# ATTAMI-V0_00.net
KiCad netlist of a schematic drawn in EAGLE
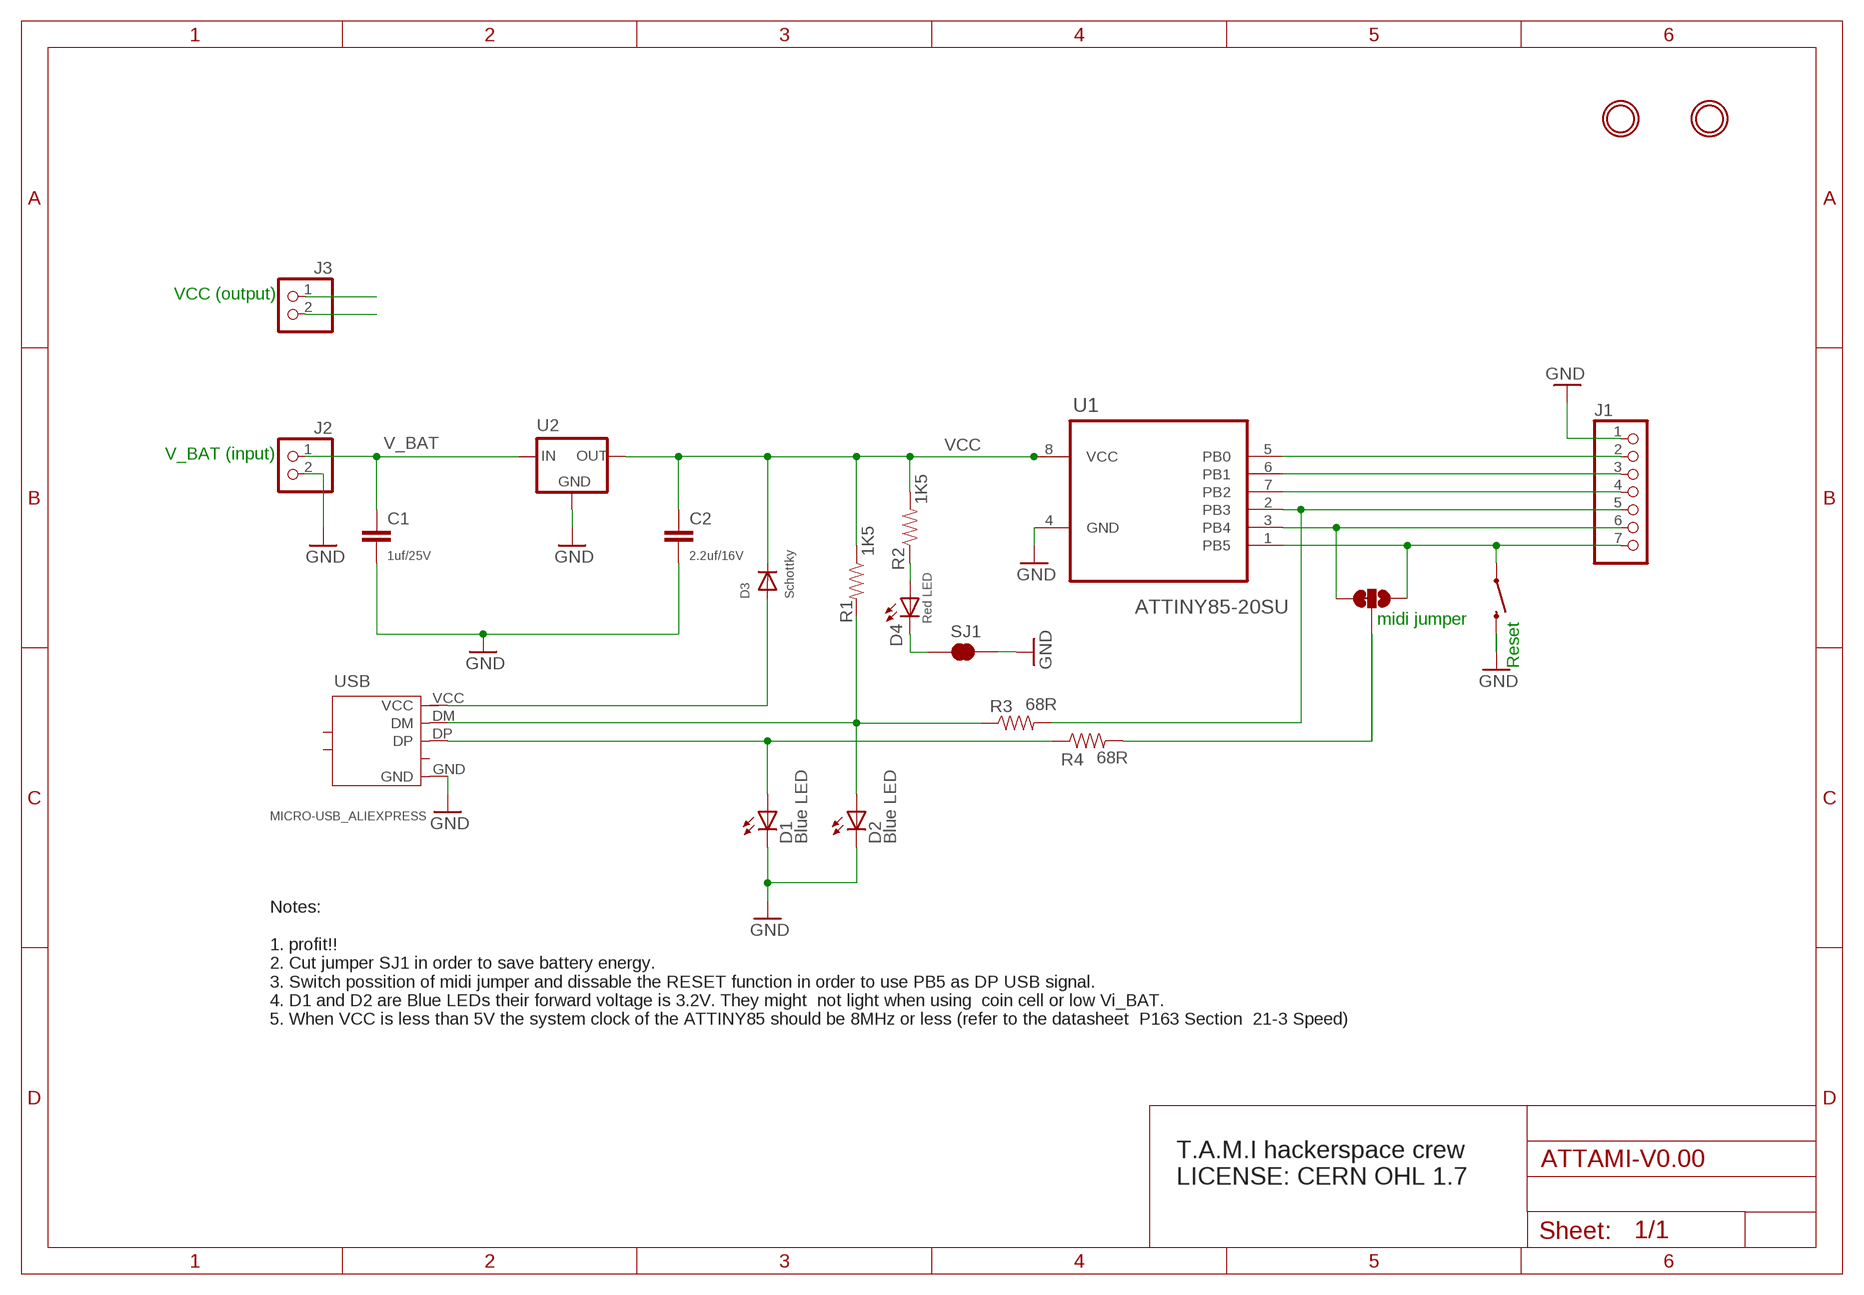
[diagram p0: schematic, sheet 1]

(export (version "E")
  (design (tool "Eeschema 10.0.6"))
  (components
    (comp (ref "C1")
      (value "1uf/25V")
      (footprint "eagle-import:0805")
      (libsource (lib "eagle-import") (part "CAP0805"))
    )
    (comp (ref "C2")
      (value "2.2uf/16V")
      (footprint "eagle-import:0805")
      (libsource (lib "eagle-import") (part "CAP0805"))
    )
    (comp (ref "D1")
      (value "Blue LED")
      (footprint "eagle-import:LED-805")
      (libsource (lib "eagle-import") (part "LED-0805"))
    )
    (comp (ref "D2")
      (value "Blue LED")
      (footprint "eagle-import:LED-805")
      (libsource (lib "eagle-import") (part "LED-0805"))
    )
    (comp (ref "D3")
      (value "Schottky")
      (footprint "eagle-import:SOD-323")
      (libsource (lib "eagle-import") (part "SCHOTTKY-DIODESOD-323"))
    )
    (comp (ref "D4")
      (value "Red LED")
      (footprint "eagle-import:LED-805")
      (libsource (lib "eagle-import") (part "LED-0805"))
    )
    (comp (ref "J1")
      (value "HEADER-1X7ROUND")
      (footprint "eagle-import:1X07_ROUND")
      (libsource (lib "eagle-import") (part "HEADER-1X7ROUND"))
    )
    (comp (ref "J2")
      (value "HEADER-1X2ROUND")
      (footprint "eagle-import:1X02_ROUND")
      (libsource (lib "eagle-import") (part "HEADER-1X2ROUND"))
    )
    (comp (ref "J3")
      (value "HEADER-1X2ROUND")
      (footprint "eagle-import:1X02_ROUND")
      (libsource (lib "eagle-import") (part "HEADER-1X2ROUND"))
    )
    (comp (ref "MIDI")
      (value "JUMPER-PAD-3-2OF3_NC_BY_TRACE_SMALL")
      (footprint "eagle-import:PAD-JUMPER-3-2OF3_NC_BY_TRACE_YES_SILK_FULL_BOX")
      (libsource (lib "eagle-import") (part "JUMPER-PAD-3-2OF3_NC_BY_TRACE_SMALL"))
    )
    (comp (ref "R1")
      (value "1K5")
      (footprint "eagle-import:0805")
      (libsource (lib "eagle-import") (part "RESISTOR0805-RES"))
    )
    (comp (ref "R2")
      (value "1K5")
      (footprint "eagle-import:0805")
      (libsource (lib "eagle-import") (part "RESISTOR0805-RES"))
    )
    (comp (ref "R3")
      (value "68R")
      (footprint "eagle-import:0805")
      (libsource (lib "eagle-import") (part "RESISTOR0805-RES"))
    )
    (comp (ref "R4")
      (value "68R")
      (footprint "eagle-import:0805")
      (libsource (lib "eagle-import") (part "RESISTOR0805-RES"))
    )
    (comp (ref "S1")
      (value "SWITCH-MOMENTARY-2-SMD-1101NE")
      (footprint "eagle-import:TACTILE-SWITCH-1101NE")
      (libsource (lib "eagle-import") (part "SWITCH-MOMENTARY-2-SMD-1101NE"))
    )
    (comp (ref "SJ1")
      (value "JUMPER-PAD-2-NC_BY_TRACE")
      (footprint "eagle-import:PAD-JUMPER-2-NC_BY_TRACE_YES_SILK")
      (libsource (lib "eagle-import") (part "JUMPER-PAD-2-NC_BY_TRACE"))
    )
    (comp (ref "U$1")
      (value "MOUNTINGHOLE2.0")
      (footprint "eagle-import:MOUNTINGHOLE_2.0_PLATED")
      (libsource (lib "eagle-import") (part "MOUNTINGHOLE2.0"))
    )
    (comp (ref "U$2")
      (value "MOUNTINGHOLE2.0")
      (footprint "eagle-import:MOUNTINGHOLE_2.0_PLATED")
      (libsource (lib "eagle-import") (part "MOUNTINGHOLE2.0"))
    )
    (comp (ref "U1")
      (value "ATTINY85-20SU")
      (footprint "eagle-import:SOIC127P798X216-8N")
      (libsource (lib "eagle-import") (part "ATTINY85-20SU"))
    )
    (comp (ref "U2")
      (value "XXX1117SOT-232")
      (footprint "eagle-import:SOT-223")
      (libsource (lib "eagle-import") (part "XXX1117SOT-232"))
    )
    (comp (ref "USB")
      (value "MICRO-USB_ALIEXPRESS")
      (footprint "eagle-import:USB-MICRO-ALIEXPRESS")
      (libsource (lib "eagle-import") (part "MICRO-USB_ALIEXPRESS"))
    )
  )
  (nets
    (net (code "1") (name "/VCC") (class "Default")
      (node (ref "C2") (pin "1") (pinfunction "1_1") (pintype "passive"))
      (node (ref "D3") (pin "CQ") (pinfunction "C_CQ") (pintype "passive"))
      (node (ref "J3") (pin "1") (pinfunction "1_1") (pintype "passive"))
      (node (ref "R1") (pin "1") (pinfunction "1_1") (pintype "passive"))
      (node (ref "R2") (pin "2") (pinfunction "2_2") (pintype "passive"))
      (node (ref "U1") (pin "8") (pinfunction "VCC_8") (pintype "power_in"))
      (node (ref "U2") (pin "2") (pinfunction "OUT_2") (pintype "passive"))
      (node (ref "U2") (pin "4") (pinfunction "OUT_4") (pintype "passive"))
    )
    (net (code "2") (name "/V_BAT") (class "Default")
      (node (ref "C1") (pin "1") (pinfunction "1_1") (pintype "passive"))
      (node (ref "J2") (pin "1") (pinfunction "1_1") (pintype "passive"))
      (node (ref "U2") (pin "3") (pinfunction "IN_3") (pintype "input"))
    )
    (net (code "3") (name "GND") (class "Default")
      (node (ref "C1") (pin "2") (pinfunction "2_2") (pintype "passive"))
      (node (ref "C2") (pin "2") (pinfunction "2_2") (pintype "passive"))
      (node (ref "D1") (pin "C") (pinfunction "C_C") (pintype "passive"))
      (node (ref "D2") (pin "C") (pinfunction "C_C") (pintype "passive"))
      (node (ref "J1") (pin "1") (pinfunction "1_1") (pintype "passive"))
      (node (ref "J2") (pin "2") (pinfunction "2_2") (pintype "passive"))
      (node (ref "J3") (pin "2") (pinfunction "2_2") (pintype "passive"))
      (node (ref "S1") (pin "P$2") (pinfunction "2_P$2") (pintype "passive"))
      (node (ref "SJ1") (pin "1") (pinfunction "1_1") (pintype "passive"))
      (node (ref "U1") (pin "4") (pinfunction "GND_4") (pintype "passive"))
      (node (ref "U2") (pin "1") (pinfunction "GND_1") (pintype "input"))
      (node (ref "USB") (pin "GND") (pinfunction "GND_GND") (pintype "bidirectional"))
    )
    (net (code "4") (name "Net-(D1-PadA)") (class "Default")
      (node (ref "D1") (pin "A") (pinfunction "A_A") (pintype "passive"))
      (node (ref "R4") (pin "1") (pinfunction "1_1") (pintype "passive"))
      (node (ref "USB") (pin "DP") (pinfunction "DP_DP") (pintype "bidirectional"))
    )
    (net (code "5") (name "Net-(D2-PadA)") (class "Default")
      (node (ref "D2") (pin "A") (pinfunction "A_A") (pintype "passive"))
      (node (ref "R1") (pin "2") (pinfunction "2_2") (pintype "passive"))
      (node (ref "R3") (pin "1") (pinfunction "1_1") (pintype "passive"))
      (node (ref "USB") (pin "DM") (pinfunction "DM_DM") (pintype "bidirectional"))
    )
    (net (code "6") (name "Net-(D3-A)") (class "Default")
      (node (ref "D3") (pin "AQ") (pinfunction "A_AQ") (pintype "passive"))
      (node (ref "USB") (pin "VCC") (pinfunction "VCC_VCC") (pintype "bidirectional"))
    )
    (net (code "7") (name "Net-(D4-PadA)") (class "Default")
      (node (ref "D4") (pin "A") (pinfunction "A_A") (pintype "passive"))
      (node (ref "R2") (pin "1") (pinfunction "1_1") (pintype "passive"))
    )
    (net (code "8") (name "Net-(D4-PadC)") (class "Default")
      (node (ref "D4") (pin "C") (pinfunction "C_C") (pintype "passive"))
      (node (ref "SJ1") (pin "2") (pinfunction "2_2") (pintype "passive"))
    )
    (net (code "9") (name "Net-(MIDI-Pad2)") (class "Default")
      (node (ref "MIDI") (pin "2") (pinfunction "2_2") (pintype "passive"))
      (node (ref "R4") (pin "2") (pinfunction "2_2") (pintype "passive"))
    )
    (net (code "10") (name "Net-(S1-1)") (class "Default")
      (node (ref "J1") (pin "7") (pinfunction "7_7") (pintype "passive"))
      (node (ref "MIDI") (pin "1") (pinfunction "1_1") (pintype "passive"))
      (node (ref "S1") (pin "P$1") (pinfunction "1_P$1") (pintype "passive"))
      (node (ref "U1") (pin "1") (pinfunction "PB5_1") (pintype "bidirectional"))
    )
    (net (code "11") (name "Net-(U1-PB0)") (class "Default")
      (node (ref "J1") (pin "2") (pinfunction "2_2") (pintype "passive"))
      (node (ref "U1") (pin "5") (pinfunction "PB0_5") (pintype "bidirectional"))
    )
    (net (code "12") (name "Net-(U1-PB1)") (class "Default")
      (node (ref "J1") (pin "3") (pinfunction "3_3") (pintype "passive"))
      (node (ref "U1") (pin "6") (pinfunction "PB1_6") (pintype "bidirectional"))
    )
    (net (code "13") (name "Net-(U1-PB2)") (class "Default")
      (node (ref "J1") (pin "4") (pinfunction "4_4") (pintype "passive"))
      (node (ref "U1") (pin "7") (pinfunction "PB2_7") (pintype "bidirectional"))
    )
    (net (code "14") (name "Net-(U1-PB3)") (class "Default")
      (node (ref "J1") (pin "5") (pinfunction "5_5") (pintype "passive"))
      (node (ref "R3") (pin "2") (pinfunction "2_2") (pintype "passive"))
      (node (ref "U1") (pin "2") (pinfunction "PB3_2") (pintype "bidirectional"))
    )
    (net (code "15") (name "Net-(U1-PB4)") (class "Default")
      (node (ref "J1") (pin "6") (pinfunction "6_6") (pintype "passive"))
      (node (ref "MIDI") (pin "3") (pinfunction "3_3") (pintype "passive"))
      (node (ref "U1") (pin "3") (pinfunction "PB4_3") (pintype "bidirectional"))
    )
  )
)
